# LEVELSHIFTER_REV01.net
KiCad netlist of a schematic drawn in EAGLE
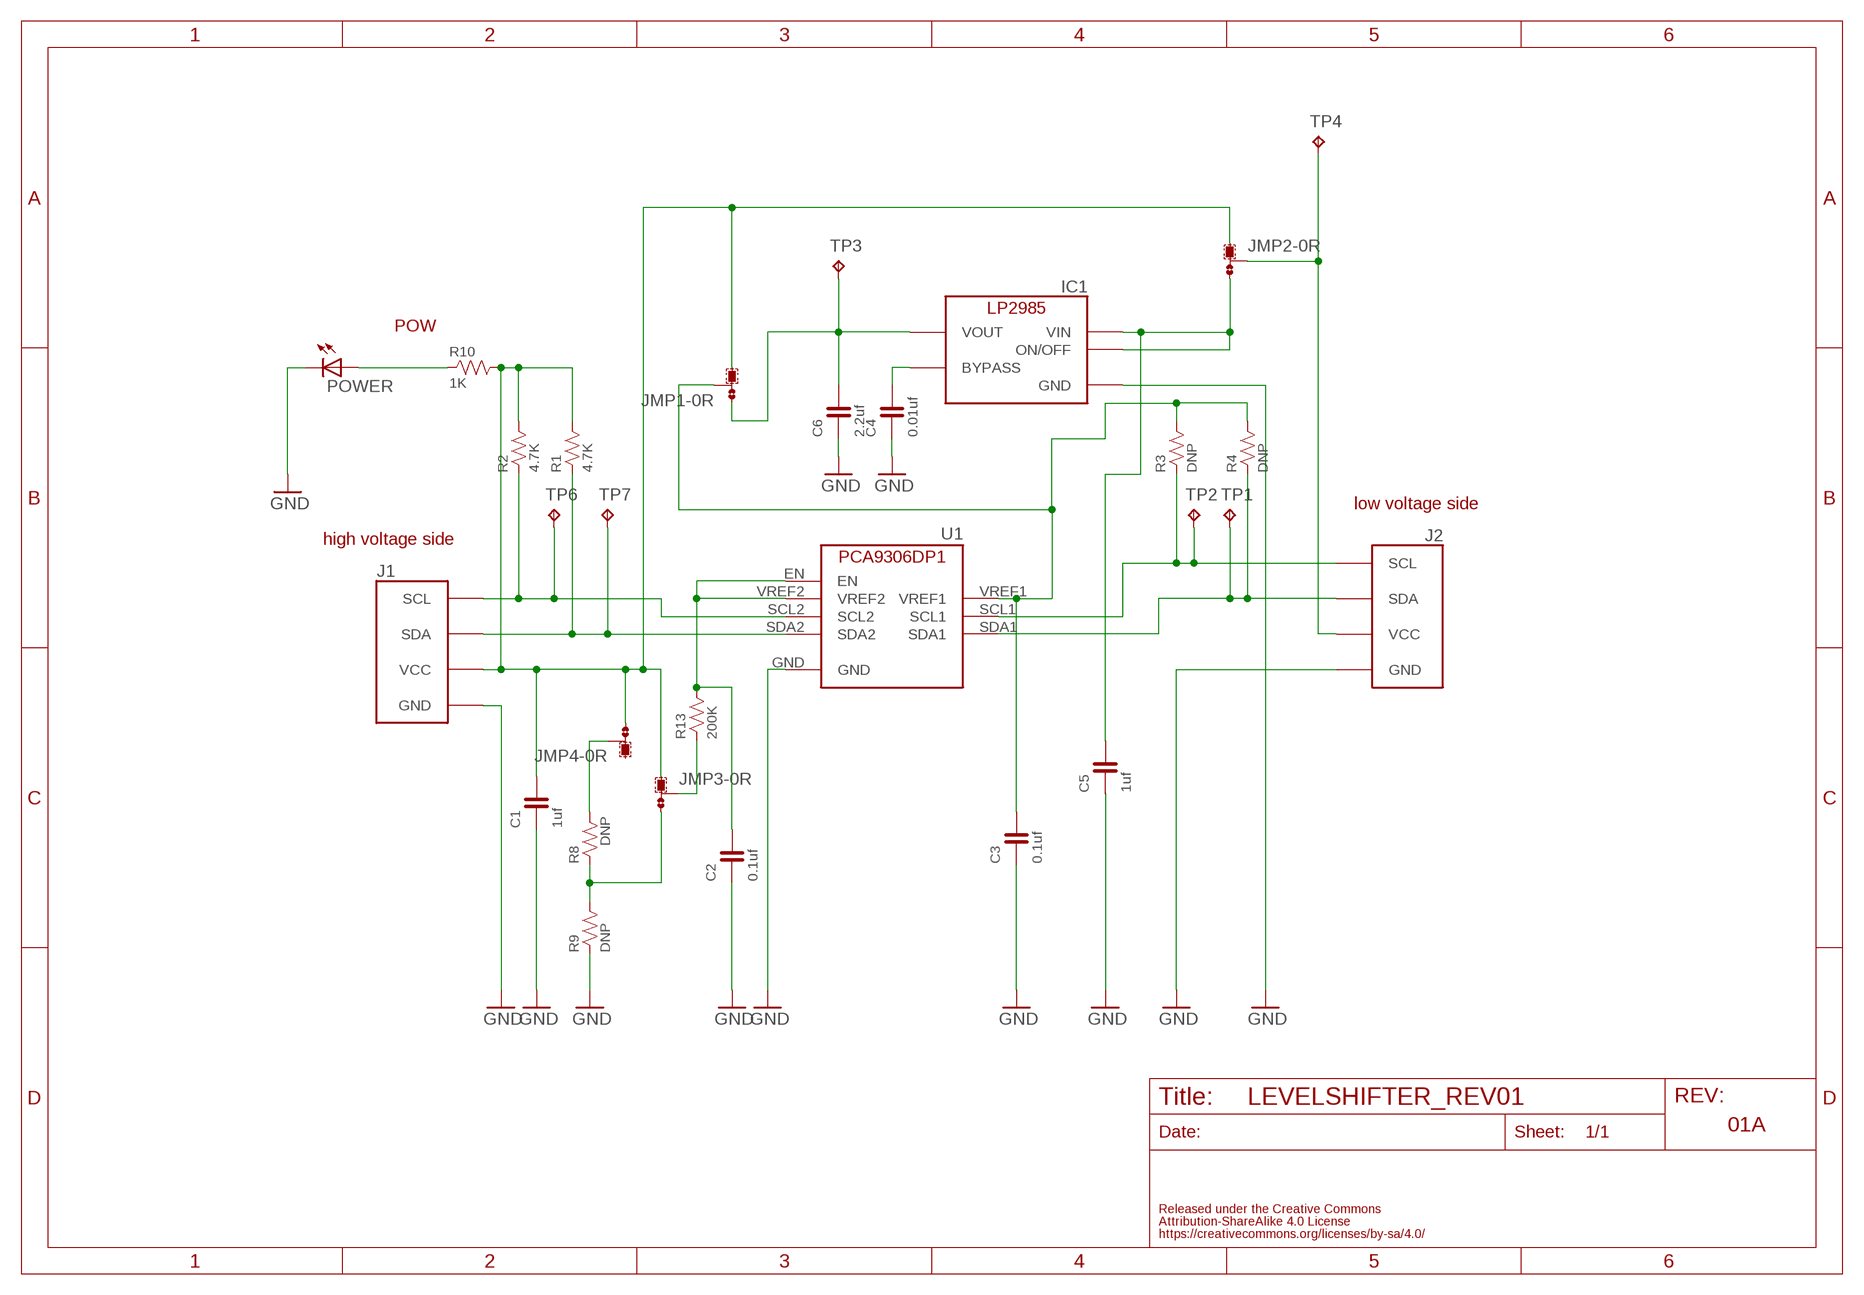
[diagram p0: schematic, sheet 1]

(export (version "E")
  (design (tool "Eeschema 10.0.6"))
  (components
    (comp (ref "C1")
      (value "1uf")
      (footprint "eagle-import:0603")
      (libsource (lib "eagle-import") (part "CAPACITOR-0603"))
    )
    (comp (ref "C2")
      (value "0.1uf")
      (footprint "eagle-import:0603")
      (libsource (lib "eagle-import") (part "CAPACITOR-0603"))
    )
    (comp (ref "C3")
      (value "0.1uf")
      (footprint "eagle-import:0603")
      (libsource (lib "eagle-import") (part "CAPACITOR-0603"))
    )
    (comp (ref "C4")
      (value "0.01uf")
      (footprint "eagle-import:0603")
      (libsource (lib "eagle-import") (part "CAPACITOR-0603"))
    )
    (comp (ref "C5")
      (value "1uf")
      (footprint "eagle-import:0603")
      (libsource (lib "eagle-import") (part "CAPACITOR-0603"))
    )
    (comp (ref "C6")
      (value "2.2uf")
      (footprint "eagle-import:0603")
      (libsource (lib "eagle-import") (part "CAPACITOR-0603"))
    )
    (comp (ref "IC1")
      (value "LP2985-33DBV")
      (footprint "eagle-import:SOT-23-5")
      (libsource (lib "eagle-import") (part "LP2985-33DBV"))
    )
    (comp (ref "J1")
      (value "FABO_BRICK_I2C-S04B-PASK-2")
      (footprint "eagle-import:FABO_BRICK_I2C_S04B-PASK-2")
      (libsource (lib "eagle-import") (part "FABO_BRICK_I2C-S04B-PASK-2"))
    )
    (comp (ref "J2")
      (value "FABO_BRICK_I2C-S04B-PASK-2")
      (footprint "eagle-import:FABO_BRICK_I2C_S04B-PASK-2")
      (libsource (lib "eagle-import") (part "FABO_BRICK_I2C-S04B-PASK-2"))
    )
    (comp (ref "JMP1")
      (value "0R-JUMPA")
      (footprint "eagle-import:A0R-JMP")
      (libsource (lib "eagle-import") (part "0R-JUMPA"))
    )
    (comp (ref "JMP2")
      (value "0R-JUMPA")
      (footprint "eagle-import:A0R-JMP")
      (libsource (lib "eagle-import") (part "0R-JUMPA"))
    )
    (comp (ref "JMP3")
      (value "0R-JUMPA")
      (footprint "eagle-import:A0R-JMP")
      (libsource (lib "eagle-import") (part "0R-JUMPA"))
    )
    (comp (ref "JMP4")
      (value "0R-JUMPA")
      (footprint "eagle-import:A0R-JMP")
      (libsource (lib "eagle-import") (part "0R-JUMPA"))
    )
    (comp (ref "POWER")
      (value "LEDCHIPLED_0603")
      (footprint "eagle-import:CHIPLED_0603")
      (libsource (lib "eagle-import") (part "LEDCHIPLED_0603"))
    )
    (comp (ref "R1")
      (value "4.7K")
      (footprint "eagle-import:0603")
      (libsource (lib "eagle-import") (part "RESISTOR-0603"))
    )
    (comp (ref "R2")
      (value "4.7K")
      (footprint "eagle-import:0603")
      (libsource (lib "eagle-import") (part "RESISTOR-0603"))
    )
    (comp (ref "R3")
      (value "DNP")
      (footprint "eagle-import:0603")
      (libsource (lib "eagle-import") (part "RESISTOR-0603"))
    )
    (comp (ref "R4")
      (value "DNP")
      (footprint "eagle-import:0603")
      (libsource (lib "eagle-import") (part "RESISTOR-0603"))
    )
    (comp (ref "R8")
      (value "DNP")
      (footprint "eagle-import:0603")
      (libsource (lib "eagle-import") (part "RESISTOR-0603"))
    )
    (comp (ref "R9")
      (value "DNP")
      (footprint "eagle-import:0603")
      (libsource (lib "eagle-import") (part "RESISTOR-0603"))
    )
    (comp (ref "R10")
      (value "1K")
      (footprint "eagle-import:0603")
      (libsource (lib "eagle-import") (part "RESISTOR-0603"))
    )
    (comp (ref "R13")
      (value "200K")
      (footprint "eagle-import:0603")
      (libsource (lib "eagle-import") (part "RESISTOR-0603"))
    )
    (comp (ref "TP1")
      (value "TPTP11R")
      (footprint "eagle-import:TP11R")
      (libsource (lib "eagle-import") (part "TPTP11R"))
    )
    (comp (ref "TP2")
      (value "TPTP11R")
      (footprint "eagle-import:TP11R")
      (libsource (lib "eagle-import") (part "TPTP11R"))
    )
    (comp (ref "TP3")
      (value "TPTP11R")
      (footprint "eagle-import:TP11R")
      (libsource (lib "eagle-import") (part "TPTP11R"))
    )
    (comp (ref "TP4")
      (value "TPTP11R")
      (footprint "eagle-import:TP11R")
      (libsource (lib "eagle-import") (part "TPTP11R"))
    )
    (comp (ref "TP6")
      (value "TPTP11R")
      (footprint "eagle-import:TP11R")
      (libsource (lib "eagle-import") (part "TPTP11R"))
    )
    (comp (ref "TP7")
      (value "TPTP11R")
      (footprint "eagle-import:TP11R")
      (libsource (lib "eagle-import") (part "TPTP11R"))
    )
    (comp (ref "U1")
      (value "PCA9306DP1")
      (footprint "eagle-import:TSSOP8")
      (libsource (lib "eagle-import") (part "PCA9306DP1"))
    )
  )
  (nets
    (net (code "1") (name "GND") (class "Default")
      (node (ref "C1") (pin "1") (pinfunction "1_1") (pintype "passive"))
      (node (ref "C2") (pin "1") (pinfunction "1_1") (pintype "passive"))
      (node (ref "C3") (pin "1") (pinfunction "1_1") (pintype "passive"))
      (node (ref "C4") (pin "1") (pinfunction "1_1") (pintype "passive"))
      (node (ref "C5") (pin "1") (pinfunction "1_1") (pintype "passive"))
      (node (ref "C6") (pin "1") (pinfunction "1_1") (pintype "passive"))
      (node (ref "IC1") (pin "2") (pinfunction "GND_2") (pintype "power_in"))
      (node (ref "J1") (pin "GND") (pinfunction "GND_GND") (pintype "bidirectional"))
      (node (ref "J2") (pin "GND") (pinfunction "GND_GND") (pintype "bidirectional"))
      (node (ref "POWER") (pin "C") (pinfunction "C_C") (pintype "passive"))
      (node (ref "R9") (pin "1") (pinfunction "1_1") (pintype "bidirectional"))
      (node (ref "U1") (pin "GND") (pinfunction "GND_GND") (pintype "bidirectional"))
    )
    (net (code "2") (name "Net-(C1-Pad2)") (class "Default")
      (node (ref "C1") (pin "2") (pinfunction "2_2") (pintype "passive"))
      (node (ref "J1") (pin "VCC") (pinfunction "VCC_VCC") (pintype "bidirectional"))
      (node (ref "JMP1") (pin "3") (pinfunction "3_3") (pintype "passive"))
      (node (ref "JMP2") (pin "1") (pinfunction "1_1") (pintype "passive"))
      (node (ref "JMP3") (pin "1") (pinfunction "1_1") (pintype "passive"))
      (node (ref "JMP4") (pin "3") (pinfunction "3_3") (pintype "passive"))
      (node (ref "R1") (pin "2") (pinfunction "2_2") (pintype "bidirectional"))
      (node (ref "R10") (pin "2") (pinfunction "2_2") (pintype "bidirectional"))
      (node (ref "R2") (pin "2") (pinfunction "2_2") (pintype "bidirectional"))
    )
    (net (code "3") (name "Net-(C2-Pad2)") (class "Default")
      (node (ref "C2") (pin "2") (pinfunction "2_2") (pintype "passive"))
      (node (ref "R13") (pin "2") (pinfunction "2_2") (pintype "bidirectional"))
      (node (ref "U1") (pin "EN") (pinfunction "EN_EN") (pintype "bidirectional"))
      (node (ref "U1") (pin "VREF2") (pinfunction "VREF2_VREF2") (pintype "bidirectional"))
    )
    (net (code "4") (name "Net-(C3-Pad2)") (class "Default")
      (node (ref "C3") (pin "2") (pinfunction "2_2") (pintype "passive"))
      (node (ref "JMP1") (pin "2") (pinfunction "2_2") (pintype "passive"))
      (node (ref "R3") (pin "2") (pinfunction "2_2") (pintype "bidirectional"))
      (node (ref "R4") (pin "2") (pinfunction "2_2") (pintype "bidirectional"))
      (node (ref "U1") (pin "VREF1") (pinfunction "VREF1_VREF1") (pintype "bidirectional"))
    )
    (net (code "5") (name "Net-(IC1-BYPASS)") (class "Default")
      (node (ref "C4") (pin "2") (pinfunction "2_2") (pintype "passive"))
      (node (ref "IC1") (pin "4") (pinfunction "BYPASS_4") (pintype "bidirectional"))
    )
    (net (code "6") (name "Net-(IC1-ON{slash}OFF)") (class "Default")
      (node (ref "C5") (pin "2") (pinfunction "2_2") (pintype "passive"))
      (node (ref "IC1") (pin "1") (pinfunction "VIN_1") (pintype "input"))
      (node (ref "IC1") (pin "3") (pinfunction "ON/OFF_3") (pintype "input"))
      (node (ref "JMP2") (pin "3") (pinfunction "3_3") (pintype "passive"))
    )
    (net (code "7") (name "Net-(IC1-VOUT)") (class "Default")
      (node (ref "C6") (pin "2") (pinfunction "2_2") (pintype "passive"))
      (node (ref "IC1") (pin "5") (pinfunction "VOUT_5") (pintype "output"))
      (node (ref "JMP1") (pin "1") (pinfunction "1_1") (pintype "passive"))
      (node (ref "TP3") (pin "TP") (pinfunction "TP_TP") (pintype "input"))
    )
    (net (code "8") (name "Net-(J1-PadSCL)") (class "Default")
      (node (ref "J1") (pin "SCL") (pinfunction "SCL_SCL") (pintype "bidirectional"))
      (node (ref "R2") (pin "1") (pinfunction "1_1") (pintype "bidirectional"))
      (node (ref "TP6") (pin "TP") (pinfunction "TP_TP") (pintype "input"))
      (node (ref "U1") (pin "SCL2") (pinfunction "SCL2_SCL2") (pintype "bidirectional"))
    )
    (net (code "9") (name "Net-(J1-PadSDA)") (class "Default")
      (node (ref "J1") (pin "SDA") (pinfunction "SDA_SDA") (pintype "bidirectional"))
      (node (ref "R1") (pin "1") (pinfunction "1_1") (pintype "bidirectional"))
      (node (ref "TP7") (pin "TP") (pinfunction "TP_TP") (pintype "input"))
      (node (ref "U1") (pin "SDA2") (pinfunction "SDA2_SDA2") (pintype "bidirectional"))
    )
    (net (code "10") (name "Net-(J2-PadSCL)") (class "Default")
      (node (ref "J2") (pin "SCL") (pinfunction "SCL_SCL") (pintype "bidirectional"))
      (node (ref "R3") (pin "1") (pinfunction "1_1") (pintype "bidirectional"))
      (node (ref "TP2") (pin "TP") (pinfunction "TP_TP") (pintype "input"))
      (node (ref "U1") (pin "SCL1") (pinfunction "SCL1_SCL1") (pintype "bidirectional"))
    )
    (net (code "11") (name "Net-(J2-PadSDA)") (class "Default")
      (node (ref "J2") (pin "SDA") (pinfunction "SDA_SDA") (pintype "bidirectional"))
      (node (ref "R4") (pin "1") (pinfunction "1_1") (pintype "bidirectional"))
      (node (ref "TP1") (pin "TP") (pinfunction "TP_TP") (pintype "input"))
      (node (ref "U1") (pin "SDA1") (pinfunction "SDA1_SDA1") (pintype "bidirectional"))
    )
    (net (code "12") (name "Net-(J2-PadVCC)") (class "Default")
      (node (ref "J2") (pin "VCC") (pinfunction "VCC_VCC") (pintype "bidirectional"))
      (node (ref "JMP2") (pin "2") (pinfunction "2_2") (pintype "passive"))
      (node (ref "TP4") (pin "TP") (pinfunction "TP_TP") (pintype "input"))
    )
    (net (code "13") (name "Net-(JMP3-Pad2)") (class "Default")
      (node (ref "JMP3") (pin "2") (pinfunction "2_2") (pintype "passive"))
      (node (ref "R13") (pin "1") (pinfunction "1_1") (pintype "bidirectional"))
    )
    (net (code "14") (name "Net-(JMP3-Pad3)") (class "Default")
      (node (ref "JMP3") (pin "3") (pinfunction "3_3") (pintype "passive"))
      (node (ref "R8") (pin "1") (pinfunction "1_1") (pintype "bidirectional"))
      (node (ref "R9") (pin "2") (pinfunction "2_2") (pintype "bidirectional"))
    )
    (net (code "15") (name "Net-(JMP4-Pad2)") (class "Default")
      (node (ref "JMP4") (pin "2") (pinfunction "2_2") (pintype "passive"))
      (node (ref "R8") (pin "2") (pinfunction "2_2") (pintype "bidirectional"))
    )
    (net (code "16") (name "Net-(POWER-PadA)") (class "Default")
      (node (ref "POWER") (pin "A") (pinfunction "A_A") (pintype "passive"))
      (node (ref "R10") (pin "1") (pinfunction "1_1") (pintype "bidirectional"))
    )
    (net (code "17") (name "unconnected-(JMP4-Pad1)") (class "Default")
      (node (ref "JMP4") (pin "1") (pinfunction "1_1") (pintype "passive"))
    )
  )
)
